# Wireless.net
KiCad netlist of a schematic drawn in Altium Designer
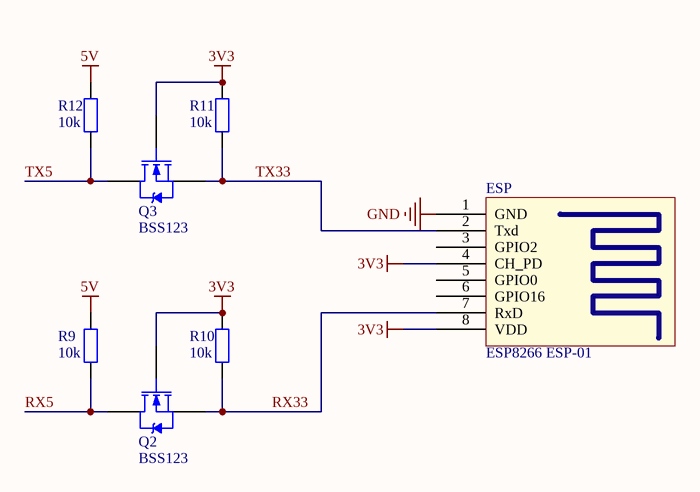
[diagram p0: Wireless.SchDoc]

(export (version "E")
  (design (tool "Eeschema 10.0.6"))
  (components
    (comp (ref "ESP")
      (value "ESP8266 ESP-01")
      (footprint "ESP8266 ESP-01")
      (description "Embase PCB, Carte-à-carte, 2.54 mm, 2 Rangée(s), 8 Contact(s), Montage traversant, Série 2214S")
      (libsource (lib "MGLib_v2") (part "ESP8266 ESP-01"))
    )
    (comp (ref "Q2")
      (value "BSS123")
      (footprint "SOT23-3")
      (description "MOSFET de puissance, Canal N, 100 V, 170 mA, 1.2 ohm, SOT-23, Montage en surface")
      (fields (field (name "VOLTAGE") "100V"))
      (libsource (lib "MGLib") (part "=RefFabricant"))
    )
    (comp (ref "Q3")
      (value "BSS123")
      (footprint "SOT23-3")
      (description "MOSFET de puissance, Canal N, 100 V, 170 mA, 1.2 ohm, SOT-23, Montage en surface")
      (fields (field (name "VOLTAGE") "100V"))
      (libsource (lib "MGLib") (part "=RefFabricant"))
    )
    (comp (ref "R9")
      (value "10k")
      (footprint "0805-R")
      (description "Résistance à puce CMS, 10 kohm, ± 1%, 250 mW, 0805 [2012 Metric], Couche épaisse, Haute puissance")
      (fields (field (name "VOLTAGE") "150V"))
      (libsource (lib "GEII1") (part "Res"))
    )
    (comp (ref "R10")
      (value "10k")
      (footprint "0805-R")
      (description "Résistance à puce CMS, 10 kohm, ± 1%, 250 mW, 0805 [2012 Metric], Couche épaisse, Haute puissance")
      (fields (field (name "VOLTAGE") "150V"))
      (libsource (lib "GEII1") (part "Res"))
    )
    (comp (ref "R11")
      (value "10k")
      (footprint "0805-R")
      (description "Résistance à puce CMS, 10 kohm, ± 1%, 250 mW, 0805 [2012 Metric], Couche épaisse, Haute puissance")
      (fields (field (name "VOLTAGE") "150V"))
      (libsource (lib "GEII1") (part "Res"))
    )
    (comp (ref "R12")
      (value "10k")
      (footprint "0805-R")
      (description "Résistance à puce CMS, 10 kohm, ± 1%, 250 mW, 0805 [2012 Metric], Couche épaisse, Haute puissance")
      (fields (field (name "VOLTAGE") "150V"))
      (libsource (lib "GEII1") (part "Res"))
    )
  )
  (nets
    (net (code "1") (name "/RX5") (class "Default")
      (node (ref "Q2") (pin "3") (pinfunction "D_3") (pintype "passive"))
      (node (ref "R9") (pin "2") (pinfunction "2_2") (pintype "passive"))
    )
    (net (code "2") (name "/RX33") (class "Default")
      (node (ref "ESP") (pin "7") (pinfunction "RxD_7") (pintype "passive"))
      (node (ref "Q2") (pin "2") (pinfunction "S_2") (pintype "passive"))
      (node (ref "R10") (pin "2") (pinfunction "2_2") (pintype "passive"))
    )
    (net (code "3") (name "/TX5") (class "Default")
      (node (ref "Q3") (pin "3") (pinfunction "D_3") (pintype "passive"))
      (node (ref "R12") (pin "2") (pinfunction "2_2") (pintype "passive"))
    )
    (net (code "4") (name "/TX33") (class "Default")
      (node (ref "ESP") (pin "2") (pinfunction "Txd_2") (pintype "passive"))
      (node (ref "Q3") (pin "2") (pinfunction "S_2") (pintype "passive"))
      (node (ref "R11") (pin "2") (pinfunction "2_2") (pintype "passive"))
    )
    (net (code "5") (name "3V3") (class "Default")
      (node (ref "ESP") (pin "4") (pinfunction "CH_PD_4") (pintype "passive"))
      (node (ref "ESP") (pin "8") (pinfunction "VDD_8") (pintype "passive"))
      (node (ref "Q2") (pin "1") (pinfunction "G_1") (pintype "passive"))
      (node (ref "Q3") (pin "1") (pinfunction "G_1") (pintype "passive"))
      (node (ref "R10") (pin "1") (pinfunction "1_1") (pintype "passive"))
      (node (ref "R11") (pin "1") (pinfunction "1_1") (pintype "passive"))
    )
    (net (code "6") (name "5V") (class "Default")
      (node (ref "R12") (pin "1") (pinfunction "1_1") (pintype "passive"))
      (node (ref "R9") (pin "1") (pinfunction "1_1") (pintype "passive"))
    )
    (net (code "7") (name "GND") (class "Default")
      (node (ref "ESP") (pin "1") (pinfunction "GND_1") (pintype "passive"))
    )
    (net (code "8") (name "unconnected-(ESP-GPIO0-Pad5)") (class "Default")
      (node (ref "ESP") (pin "5") (pinfunction "GPIO0_5") (pintype "passive"))
    )
    (net (code "9") (name "unconnected-(ESP-GPIO2-Pad3)") (class "Default")
      (node (ref "ESP") (pin "3") (pinfunction "GPIO2_3") (pintype "passive"))
    )
    (net (code "10") (name "unconnected-(ESP-GPIO16-Pad6)") (class "Default")
      (node (ref "ESP") (pin "6") (pinfunction "GPIO16_6") (pintype "passive"))
    )
  )
)
